# B165A.net
KiCad netlist of a schematic drawn in EAGLE
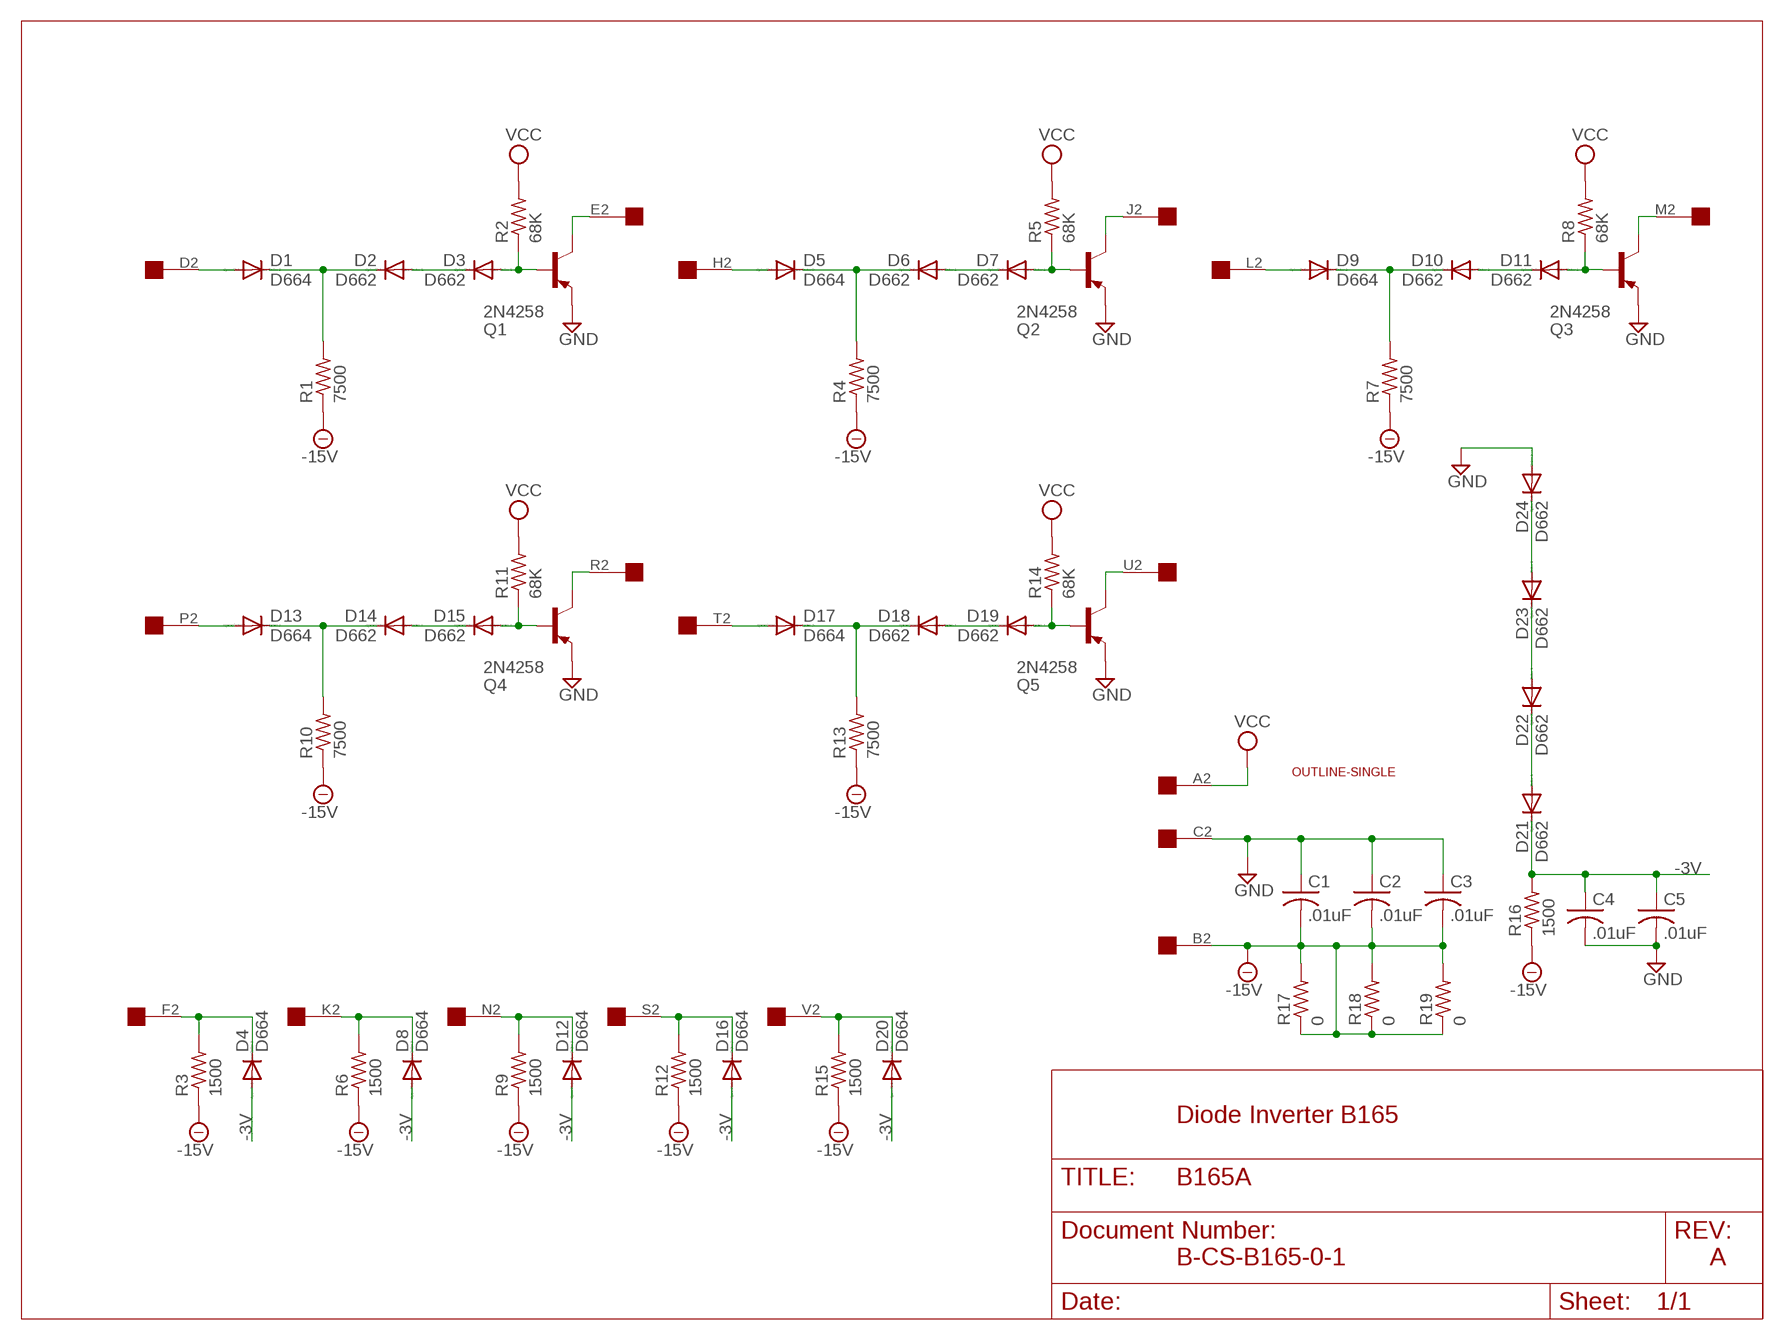
[diagram p0: schematic, sheet 1]

(export (version "E")
  (design (tool "Eeschema 10.0.6"))
  (components
    (comp (ref "C1")
      (value ".01uF")
      (footprint "eagle-import:C063-025X075")
      (libsource (lib "eagle-import") (part "C-US"))
    )
    (comp (ref "C2")
      (value ".01uF")
      (footprint "eagle-import:C063-025X075")
      (libsource (lib "eagle-import") (part "C-US"))
    )
    (comp (ref "C3")
      (value ".01uF")
      (footprint "eagle-import:C063-025X075")
      (libsource (lib "eagle-import") (part "C-US"))
    )
    (comp (ref "C4")
      (value ".01uF")
      (footprint "eagle-import:C063-025X075")
      (libsource (lib "eagle-import") (part "C-US"))
    )
    (comp (ref "C5")
      (value ".01uF")
      (footprint "eagle-import:C063-025X075")
      (libsource (lib "eagle-import") (part "C-US"))
    )
    (comp (ref "D1")
      (value "D664")
      (footprint "eagle-import:DO35-10")
      (libsource (lib "eagle-import") (part "DIODE-DO35-10"))
    )
    (comp (ref "D2")
      (value "D662")
      (footprint "eagle-import:DO35-10")
      (libsource (lib "eagle-import") (part "DIODE-DO35-10"))
    )
    (comp (ref "D3")
      (value "D662")
      (footprint "eagle-import:DO35-10")
      (libsource (lib "eagle-import") (part "DIODE-DO35-10"))
    )
    (comp (ref "D4")
      (value "D664")
      (footprint "eagle-import:DO35-10")
      (libsource (lib "eagle-import") (part "DIODE-DO35-10"))
    )
    (comp (ref "D5")
      (value "D664")
      (footprint "eagle-import:DO35-10")
      (libsource (lib "eagle-import") (part "DIODE-DO35-10"))
    )
    (comp (ref "D6")
      (value "D662")
      (footprint "eagle-import:DO35-10")
      (libsource (lib "eagle-import") (part "DIODE-DO35-10"))
    )
    (comp (ref "D7")
      (value "D662")
      (footprint "eagle-import:DO35-10")
      (libsource (lib "eagle-import") (part "DIODE-DO35-10"))
    )
    (comp (ref "D8")
      (value "D664")
      (footprint "eagle-import:DO35-10")
      (libsource (lib "eagle-import") (part "DIODE-DO35-10"))
    )
    (comp (ref "D9")
      (value "D664")
      (footprint "eagle-import:DO35-10")
      (libsource (lib "eagle-import") (part "DIODE-DO35-10"))
    )
    (comp (ref "D10")
      (value "D662")
      (footprint "eagle-import:DO35-10")
      (libsource (lib "eagle-import") (part "DIODE-DO35-10"))
    )
    (comp (ref "D11")
      (value "D662")
      (footprint "eagle-import:DO35-10")
      (libsource (lib "eagle-import") (part "DIODE-DO35-10"))
    )
    (comp (ref "D12")
      (value "D664")
      (footprint "eagle-import:DO35-10")
      (libsource (lib "eagle-import") (part "DIODE-DO35-10"))
    )
    (comp (ref "D13")
      (value "D664")
      (footprint "eagle-import:DO35-10")
      (libsource (lib "eagle-import") (part "DIODE-DO35-10"))
    )
    (comp (ref "D14")
      (value "D662")
      (footprint "eagle-import:DO35-10")
      (libsource (lib "eagle-import") (part "DIODE-DO35-10"))
    )
    (comp (ref "D15")
      (value "D662")
      (footprint "eagle-import:DO35-10")
      (libsource (lib "eagle-import") (part "DIODE-DO35-10"))
    )
    (comp (ref "D16")
      (value "D664")
      (footprint "eagle-import:DO35-10")
      (libsource (lib "eagle-import") (part "DIODE-DO35-10"))
    )
    (comp (ref "D17")
      (value "D664")
      (footprint "eagle-import:DO35-10")
      (libsource (lib "eagle-import") (part "DIODE-DO35-10"))
    )
    (comp (ref "D18")
      (value "D662")
      (footprint "eagle-import:DO35-10")
      (libsource (lib "eagle-import") (part "DIODE-DO35-10"))
    )
    (comp (ref "D19")
      (value "D662")
      (footprint "eagle-import:DO35-10")
      (libsource (lib "eagle-import") (part "DIODE-DO35-10"))
    )
    (comp (ref "D20")
      (value "D664")
      (footprint "eagle-import:DO35-10")
      (libsource (lib "eagle-import") (part "DIODE-DO35-10"))
    )
    (comp (ref "D21")
      (value "D662")
      (footprint "eagle-import:DO35-10")
      (libsource (lib "eagle-import") (part "DIODE-DO35-10"))
    )
    (comp (ref "D22")
      (value "D662")
      (footprint "eagle-import:DO35-10")
      (libsource (lib "eagle-import") (part "DIODE-DO35-10"))
    )
    (comp (ref "D23")
      (value "D662")
      (footprint "eagle-import:DO35-10")
      (libsource (lib "eagle-import") (part "DIODE-DO35-10"))
    )
    (comp (ref "D24")
      (value "D662")
      (footprint "eagle-import:DO35-10")
      (libsource (lib "eagle-import") (part "DIODE-DO35-10"))
    )
    (comp (ref "Q1")
      (value "2N4258")
      (footprint "eagle-import:TO5")
      (libsource (lib "eagle-import") (part "-PNP-TO5"))
    )
    (comp (ref "Q2")
      (value "2N4258")
      (footprint "eagle-import:TO5")
      (libsource (lib "eagle-import") (part "-PNP-TO5"))
    )
    (comp (ref "Q3")
      (value "2N4258")
      (footprint "eagle-import:TO5")
      (libsource (lib "eagle-import") (part "-PNP-TO5"))
    )
    (comp (ref "Q4")
      (value "2N4258")
      (footprint "eagle-import:TO5")
      (libsource (lib "eagle-import") (part "-PNP-TO5"))
    )
    (comp (ref "Q5")
      (value "2N4258")
      (footprint "eagle-import:TO5")
      (libsource (lib "eagle-import") (part "-PNP-TO5"))
    )
    (comp (ref "R1")
      (value "7500")
      (footprint "eagle-import:0207_10")
      (libsource (lib "eagle-import") (part "R-US_0207/10"))
    )
    (comp (ref "R2")
      (value "68K")
      (footprint "eagle-import:0207_10")
      (libsource (lib "eagle-import") (part "R-US_0207/10"))
    )
    (comp (ref "R3")
      (value "1500")
      (footprint "eagle-import:0207_10")
      (libsource (lib "eagle-import") (part "R-US_0207/10"))
    )
    (comp (ref "R4")
      (value "7500")
      (footprint "eagle-import:0207_10")
      (libsource (lib "eagle-import") (part "R-US_0207/10"))
    )
    (comp (ref "R5")
      (value "68K")
      (footprint "eagle-import:0207_10")
      (libsource (lib "eagle-import") (part "R-US_0207/10"))
    )
    (comp (ref "R6")
      (value "1500")
      (footprint "eagle-import:0207_10")
      (libsource (lib "eagle-import") (part "R-US_0207/10"))
    )
    (comp (ref "R7")
      (value "7500")
      (footprint "eagle-import:0207_10")
      (libsource (lib "eagle-import") (part "R-US_0207/10"))
    )
    (comp (ref "R8")
      (value "68K")
      (footprint "eagle-import:0207_10")
      (libsource (lib "eagle-import") (part "R-US_0207/10"))
    )
    (comp (ref "R9")
      (value "1500")
      (footprint "eagle-import:0207_10")
      (libsource (lib "eagle-import") (part "R-US_0207/10"))
    )
    (comp (ref "R10")
      (value "7500")
      (footprint "eagle-import:0207_10")
      (libsource (lib "eagle-import") (part "R-US_0207/10"))
    )
    (comp (ref "R11")
      (value "68K")
      (footprint "eagle-import:0207_10")
      (libsource (lib "eagle-import") (part "R-US_0207/10"))
    )
    (comp (ref "R12")
      (value "1500")
      (footprint "eagle-import:0207_10")
      (libsource (lib "eagle-import") (part "R-US_0207/10"))
    )
    (comp (ref "R13")
      (value "7500")
      (footprint "eagle-import:0207_10")
      (libsource (lib "eagle-import") (part "R-US_0207/10"))
    )
    (comp (ref "R14")
      (value "68K")
      (footprint "eagle-import:0207_10")
      (libsource (lib "eagle-import") (part "R-US_0207/10"))
    )
    (comp (ref "R15")
      (value "1500")
      (footprint "eagle-import:0207_10")
      (libsource (lib "eagle-import") (part "R-US_0207/10"))
    )
    (comp (ref "R16")
      (value "1500")
      (footprint "eagle-import:0207_10")
      (libsource (lib "eagle-import") (part "R-US_0207/10"))
    )
    (comp (ref "R17")
      (value "0")
      (footprint "eagle-import:0207_10")
      (libsource (lib "eagle-import") (part "R-US_0207/10"))
    )
    (comp (ref "R18")
      (value "0")
      (footprint "eagle-import:0207_10")
      (libsource (lib "eagle-import") (part "R-US_0207/10"))
    )
    (comp (ref "R19")
      (value "0")
      (footprint "eagle-import:0207_10")
      (libsource (lib "eagle-import") (part "R-US_0207/10"))
    )
    (comp (ref "U$1")
      (value "OUTLINE-SINGLE")
      (footprint "eagle-import:SINGLE")
      (libsource (lib "eagle-import") (part "OUTLINE-SINGLE"))
    )
    (comp (ref "U$2")
      (value "EDGE-1")
      (footprint "eagle-import:EDGE-CON1")
      (libsource (lib "eagle-import") (part "EDGE-1"))
    )
  )
  (nets
    (net (code "1") (name "-15V") (class "Default")
      (node (ref "C1") (pin "2") (pinfunction "2_2") (pintype "passive"))
      (node (ref "C2") (pin "2") (pinfunction "2_2") (pintype "passive"))
      (node (ref "C3") (pin "2") (pinfunction "2_2") (pintype "passive"))
      (node (ref "R1") (pin "1") (pinfunction "1_1") (pintype "passive"))
      (node (ref "R10") (pin "1") (pinfunction "1_1") (pintype "passive"))
      (node (ref "R12") (pin "1") (pinfunction "1_1") (pintype "passive"))
      (node (ref "R13") (pin "1") (pinfunction "1_1") (pintype "passive"))
      (node (ref "R15") (pin "1") (pinfunction "1_1") (pintype "passive"))
      (node (ref "R16") (pin "1") (pinfunction "1_1") (pintype "passive"))
      (node (ref "R17") (pin "1") (pinfunction "1_1") (pintype "passive"))
      (node (ref "R17") (pin "2") (pinfunction "2_2") (pintype "passive"))
      (node (ref "R18") (pin "1") (pinfunction "1_1") (pintype "passive"))
      (node (ref "R18") (pin "2") (pinfunction "2_2") (pintype "passive"))
      (node (ref "R19") (pin "1") (pinfunction "1_1") (pintype "passive"))
      (node (ref "R19") (pin "2") (pinfunction "2_2") (pintype "passive"))
      (node (ref "R3") (pin "1") (pinfunction "1_1") (pintype "passive"))
      (node (ref "R4") (pin "1") (pinfunction "1_1") (pintype "passive"))
      (node (ref "R6") (pin "1") (pinfunction "1_1") (pintype "passive"))
      (node (ref "R7") (pin "1") (pinfunction "1_1") (pintype "passive"))
      (node (ref "R9") (pin "1") (pinfunction "1_1") (pintype "passive"))
      (node (ref "U$2") (pin "B2") (pinfunction "1_B2") (pintype "bidirectional"))
    )
    (net (code "2") (name "/-3V") (class "Default")
      (node (ref "C4") (pin "1") (pinfunction "1_1") (pintype "passive"))
      (node (ref "C5") (pin "1") (pinfunction "1_1") (pintype "passive"))
      (node (ref "D12") (pin "A") (pinfunction "A_A") (pintype "passive"))
      (node (ref "D16") (pin "A") (pinfunction "A_A") (pintype "passive"))
      (node (ref "D20") (pin "A") (pinfunction "A_A") (pintype "passive"))
      (node (ref "D21") (pin "C") (pinfunction "C_C") (pintype "passive"))
      (node (ref "D4") (pin "A") (pinfunction "A_A") (pintype "passive"))
      (node (ref "D8") (pin "A") (pinfunction "A_A") (pintype "passive"))
      (node (ref "R16") (pin "2") (pinfunction "2_2") (pintype "passive"))
    )
    (net (code "3") (name "GND") (class "Default")
      (node (ref "C1") (pin "1") (pinfunction "1_1") (pintype "passive"))
      (node (ref "C2") (pin "1") (pinfunction "1_1") (pintype "passive"))
      (node (ref "C3") (pin "1") (pinfunction "1_1") (pintype "passive"))
      (node (ref "C4") (pin "2") (pinfunction "2_2") (pintype "passive"))
      (node (ref "C5") (pin "2") (pinfunction "2_2") (pintype "passive"))
      (node (ref "D24") (pin "A") (pinfunction "A_A") (pintype "passive"))
      (node (ref "Q1") (pin "1") (pinfunction "E_1") (pintype "passive"))
      (node (ref "Q2") (pin "1") (pinfunction "E_1") (pintype "passive"))
      (node (ref "Q3") (pin "1") (pinfunction "E_1") (pintype "passive"))
      (node (ref "Q4") (pin "1") (pinfunction "E_1") (pintype "passive"))
      (node (ref "Q5") (pin "1") (pinfunction "E_1") (pintype "passive"))
      (node (ref "U$2") (pin "C2") (pinfunction "1_C2") (pintype "bidirectional"))
    )
    (net (code "4") (name "Net-(D1-PadC)") (class "Default")
      (node (ref "D1") (pin "C") (pinfunction "C_C") (pintype "passive"))
      (node (ref "D2") (pin "C") (pinfunction "C_C") (pintype "passive"))
      (node (ref "R1") (pin "2") (pinfunction "2_2") (pintype "passive"))
    )
    (net (code "5") (name "Net-(D2-PadA)") (class "Default")
      (node (ref "D2") (pin "A") (pinfunction "A_A") (pintype "passive"))
      (node (ref "D3") (pin "C") (pinfunction "C_C") (pintype "passive"))
    )
    (net (code "6") (name "Net-(D5-PadC)") (class "Default")
      (node (ref "D5") (pin "C") (pinfunction "C_C") (pintype "passive"))
      (node (ref "D6") (pin "C") (pinfunction "C_C") (pintype "passive"))
      (node (ref "R4") (pin "2") (pinfunction "2_2") (pintype "passive"))
    )
    (net (code "7") (name "Net-(D6-PadA)") (class "Default")
      (node (ref "D6") (pin "A") (pinfunction "A_A") (pintype "passive"))
      (node (ref "D7") (pin "C") (pinfunction "C_C") (pintype "passive"))
    )
    (net (code "8") (name "Net-(D10-PadA)") (class "Default")
      (node (ref "D10") (pin "A") (pinfunction "A_A") (pintype "passive"))
      (node (ref "D11") (pin "C") (pinfunction "C_C") (pintype "passive"))
    )
    (net (code "9") (name "Net-(D10-PadC)") (class "Default")
      (node (ref "D10") (pin "C") (pinfunction "C_C") (pintype "passive"))
      (node (ref "D9") (pin "C") (pinfunction "C_C") (pintype "passive"))
      (node (ref "R7") (pin "2") (pinfunction "2_2") (pintype "passive"))
    )
    (net (code "10") (name "Net-(D13-PadC)") (class "Default")
      (node (ref "D13") (pin "C") (pinfunction "C_C") (pintype "passive"))
      (node (ref "D14") (pin "C") (pinfunction "C_C") (pintype "passive"))
      (node (ref "R10") (pin "2") (pinfunction "2_2") (pintype "passive"))
    )
    (net (code "11") (name "Net-(D14-PadA)") (class "Default")
      (node (ref "D14") (pin "A") (pinfunction "A_A") (pintype "passive"))
      (node (ref "D15") (pin "C") (pinfunction "C_C") (pintype "passive"))
    )
    (net (code "12") (name "Net-(D17-PadC)") (class "Default")
      (node (ref "D17") (pin "C") (pinfunction "C_C") (pintype "passive"))
      (node (ref "D18") (pin "C") (pinfunction "C_C") (pintype "passive"))
      (node (ref "R13") (pin "2") (pinfunction "2_2") (pintype "passive"))
    )
    (net (code "13") (name "Net-(D18-PadA)") (class "Default")
      (node (ref "D18") (pin "A") (pinfunction "A_A") (pintype "passive"))
      (node (ref "D19") (pin "C") (pinfunction "C_C") (pintype "passive"))
    )
    (net (code "14") (name "Net-(D21-PadA)") (class "Default")
      (node (ref "D21") (pin "A") (pinfunction "A_A") (pintype "passive"))
      (node (ref "D22") (pin "C") (pinfunction "C_C") (pintype "passive"))
    )
    (net (code "15") (name "Net-(D22-PadA)") (class "Default")
      (node (ref "D22") (pin "A") (pinfunction "A_A") (pintype "passive"))
      (node (ref "D23") (pin "C") (pinfunction "C_C") (pintype "passive"))
    )
    (net (code "16") (name "Net-(D23-PadA)") (class "Default")
      (node (ref "D23") (pin "A") (pinfunction "A_A") (pintype "passive"))
      (node (ref "D24") (pin "C") (pinfunction "C_C") (pintype "passive"))
    )
    (net (code "17") (name "Net-(Q1-B)") (class "Default")
      (node (ref "D3") (pin "A") (pinfunction "A_A") (pintype "passive"))
      (node (ref "Q1") (pin "2") (pinfunction "B_2") (pintype "passive"))
      (node (ref "R2") (pin "1") (pinfunction "1_1") (pintype "passive"))
    )
    (net (code "18") (name "Net-(Q1-C)") (class "Default")
      (node (ref "Q1") (pin "3") (pinfunction "C_3") (pintype "passive"))
      (node (ref "U$2") (pin "E2") (pinfunction "1_E2") (pintype "bidirectional"))
    )
    (net (code "19") (name "Net-(Q2-B)") (class "Default")
      (node (ref "D7") (pin "A") (pinfunction "A_A") (pintype "passive"))
      (node (ref "Q2") (pin "2") (pinfunction "B_2") (pintype "passive"))
      (node (ref "R5") (pin "1") (pinfunction "1_1") (pintype "passive"))
    )
    (net (code "20") (name "Net-(Q2-C)") (class "Default")
      (node (ref "Q2") (pin "3") (pinfunction "C_3") (pintype "passive"))
      (node (ref "U$2") (pin "J2") (pinfunction "1_J2") (pintype "bidirectional"))
    )
    (net (code "21") (name "Net-(Q3-B)") (class "Default")
      (node (ref "D11") (pin "A") (pinfunction "A_A") (pintype "passive"))
      (node (ref "Q3") (pin "2") (pinfunction "B_2") (pintype "passive"))
      (node (ref "R8") (pin "1") (pinfunction "1_1") (pintype "passive"))
    )
    (net (code "22") (name "Net-(Q3-C)") (class "Default")
      (node (ref "Q3") (pin "3") (pinfunction "C_3") (pintype "passive"))
      (node (ref "U$2") (pin "M2") (pinfunction "1_M2") (pintype "bidirectional"))
    )
    (net (code "23") (name "Net-(Q4-B)") (class "Default")
      (node (ref "D15") (pin "A") (pinfunction "A_A") (pintype "passive"))
      (node (ref "Q4") (pin "2") (pinfunction "B_2") (pintype "passive"))
      (node (ref "R11") (pin "1") (pinfunction "1_1") (pintype "passive"))
    )
    (net (code "24") (name "Net-(Q4-C)") (class "Default")
      (node (ref "Q4") (pin "3") (pinfunction "C_3") (pintype "passive"))
      (node (ref "U$2") (pin "R2") (pinfunction "1_R2") (pintype "bidirectional"))
    )
    (net (code "25") (name "Net-(Q5-B)") (class "Default")
      (node (ref "D19") (pin "A") (pinfunction "A_A") (pintype "passive"))
      (node (ref "Q5") (pin "2") (pinfunction "B_2") (pintype "passive"))
      (node (ref "R14") (pin "1") (pinfunction "1_1") (pintype "passive"))
    )
    (net (code "26") (name "Net-(Q5-C)") (class "Default")
      (node (ref "Q5") (pin "3") (pinfunction "C_3") (pintype "passive"))
      (node (ref "U$2") (pin "U2") (pinfunction "1_U2") (pintype "bidirectional"))
    )
    (net (code "27") (name "Net-(U$2D-1)") (class "Default")
      (node (ref "D1") (pin "A") (pinfunction "A_A") (pintype "passive"))
      (node (ref "U$2") (pin "D2") (pinfunction "1_D2") (pintype "bidirectional"))
    )
    (net (code "28") (name "Net-(U$2F-1)") (class "Default")
      (node (ref "D4") (pin "C") (pinfunction "C_C") (pintype "passive"))
      (node (ref "R3") (pin "2") (pinfunction "2_2") (pintype "passive"))
      (node (ref "U$2") (pin "F2") (pinfunction "1_F2") (pintype "bidirectional"))
    )
    (net (code "29") (name "Net-(U$2G-1)") (class "Default")
      (node (ref "D5") (pin "A") (pinfunction "A_A") (pintype "passive"))
      (node (ref "U$2") (pin "H2") (pinfunction "1_H2") (pintype "bidirectional"))
    )
    (net (code "30") (name "Net-(U$2I-1)") (class "Default")
      (node (ref "D8") (pin "C") (pinfunction "C_C") (pintype "passive"))
      (node (ref "R6") (pin "2") (pinfunction "2_2") (pintype "passive"))
      (node (ref "U$2") (pin "K2") (pinfunction "1_K2") (pintype "bidirectional"))
    )
    (net (code "31") (name "Net-(U$2J-1)") (class "Default")
      (node (ref "D9") (pin "A") (pinfunction "A_A") (pintype "passive"))
      (node (ref "U$2") (pin "L2") (pinfunction "1_L2") (pintype "bidirectional"))
    )
    (net (code "32") (name "Net-(U$2L-1)") (class "Default")
      (node (ref "D12") (pin "C") (pinfunction "C_C") (pintype "passive"))
      (node (ref "R9") (pin "2") (pinfunction "2_2") (pintype "passive"))
      (node (ref "U$2") (pin "N2") (pinfunction "1_N2") (pintype "bidirectional"))
    )
    (net (code "33") (name "Net-(U$2M-1)") (class "Default")
      (node (ref "D13") (pin "A") (pinfunction "A_A") (pintype "passive"))
      (node (ref "U$2") (pin "P2") (pinfunction "1_P2") (pintype "bidirectional"))
    )
    (net (code "34") (name "Net-(U$2O-1)") (class "Default")
      (node (ref "D16") (pin "C") (pinfunction "C_C") (pintype "passive"))
      (node (ref "R12") (pin "2") (pinfunction "2_2") (pintype "passive"))
      (node (ref "U$2") (pin "S2") (pinfunction "1_S2") (pintype "bidirectional"))
    )
    (net (code "35") (name "Net-(U$2P-1)") (class "Default")
      (node (ref "D17") (pin "A") (pinfunction "A_A") (pintype "passive"))
      (node (ref "U$2") (pin "T2") (pinfunction "1_T2") (pintype "bidirectional"))
    )
    (net (code "36") (name "Net-(U$2R-1)") (class "Default")
      (node (ref "D20") (pin "C") (pinfunction "C_C") (pintype "passive"))
      (node (ref "R15") (pin "2") (pinfunction "2_2") (pintype "passive"))
      (node (ref "U$2") (pin "V2") (pinfunction "1_V2") (pintype "bidirectional"))
    )
    (net (code "37") (name "VCC") (class "Default")
      (node (ref "R11") (pin "2") (pinfunction "2_2") (pintype "passive"))
      (node (ref "R14") (pin "2") (pinfunction "2_2") (pintype "passive"))
      (node (ref "R2") (pin "2") (pinfunction "2_2") (pintype "passive"))
      (node (ref "R5") (pin "2") (pinfunction "2_2") (pintype "passive"))
      (node (ref "R8") (pin "2") (pinfunction "2_2") (pintype "passive"))
      (node (ref "U$2") (pin "A2") (pinfunction "1_A2") (pintype "bidirectional"))
    )
  )
)
